# servo-ldr.net
KiCad netlist of a schematic drawn in EAGLE
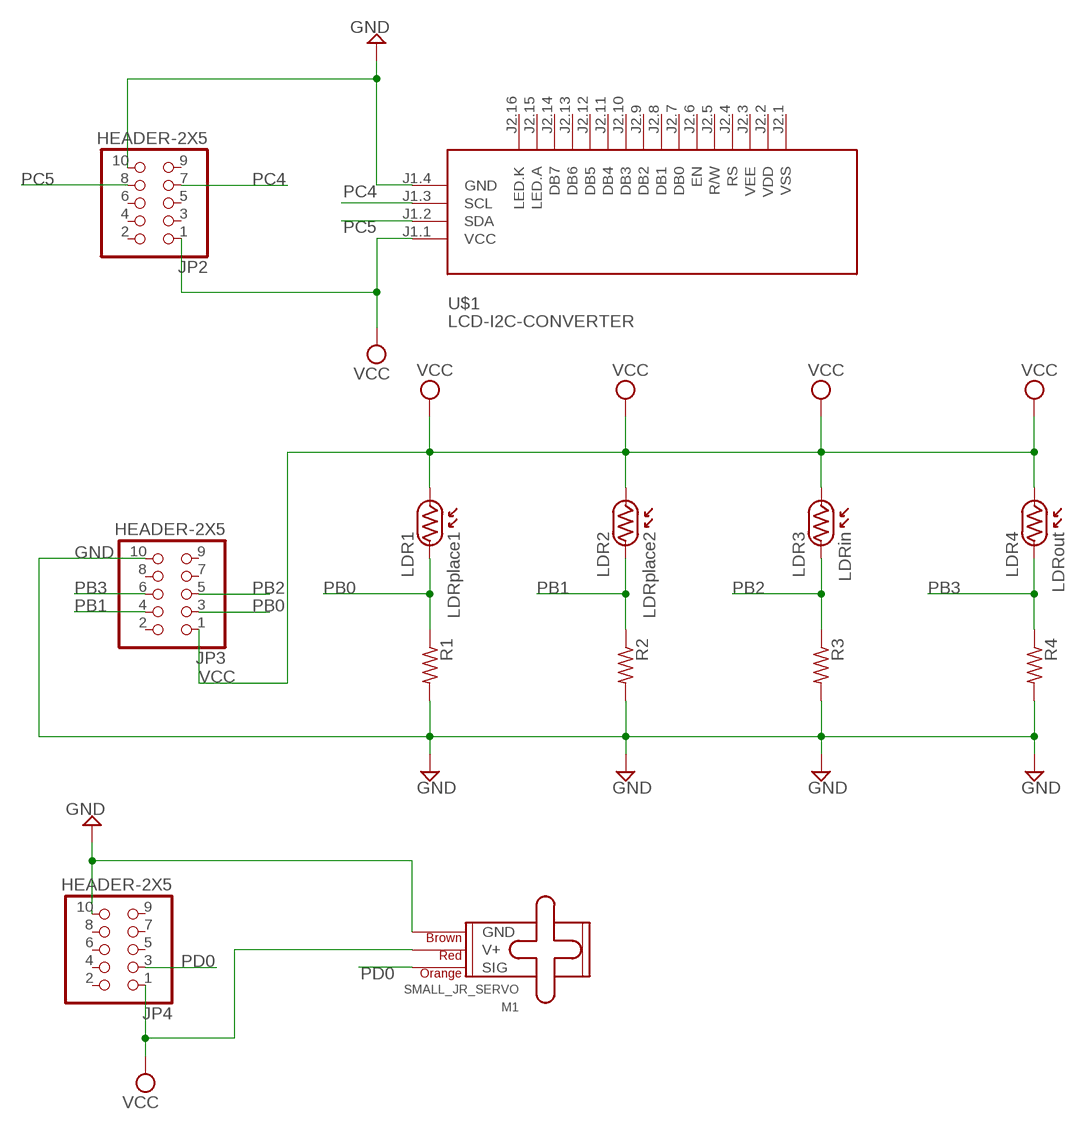
[diagram p0: schematic, sheet 1]

(export (version "E")
  (design (tool "Eeschema 10.0.6"))
  (components
    (comp (ref "JP2")
      (value "HEADER-2X5")
      (footprint "eagle-import:2X05")
      (libsource (lib "eagle-import") (part "HEADER-2X5"))
    )
    (comp (ref "JP3")
      (value "HEADER-2X5")
      (footprint "eagle-import:2X05")
      (libsource (lib "eagle-import") (part "HEADER-2X5"))
    )
    (comp (ref "JP4")
      (value "HEADER-2X5")
      (footprint "eagle-import:2X05")
      (libsource (lib "eagle-import") (part "HEADER-2X5"))
    )
    (comp (ref "LDR1")
      (value "LDRplace1")
      (footprint "eagle-import:3MM")
      (libsource (lib "eagle-import") (part "LDR"))
    )
    (comp (ref "LDR2")
      (value "LDRplace2")
      (footprint "eagle-import:3MM")
      (libsource (lib "eagle-import") (part "LDR"))
    )
    (comp (ref "LDR3")
      (value "LDRin")
      (footprint "eagle-import:3MM")
      (libsource (lib "eagle-import") (part "LDR"))
    )
    (comp (ref "LDR4")
      (value "LDRout")
      (footprint "eagle-import:3MM")
      (libsource (lib "eagle-import") (part "LDR"))
    )
    (comp (ref "M1")
      (value "SMALL_JR_SERVO")
      (footprint "eagle-import:1X03")
      (libsource (lib "eagle-import") (part "SMALL_JR_SERVO"))
    )
    (comp (ref "R1")
      (value "R-US_0207/10")
      (footprint "eagle-import:0207_10")
      (libsource (lib "eagle-import") (part "R-US_0207/10"))
    )
    (comp (ref "R2")
      (value "R-US_0207/10")
      (footprint "eagle-import:0207_10")
      (libsource (lib "eagle-import") (part "R-US_0207/10"))
    )
    (comp (ref "R3")
      (value "R-US_0207/10")
      (footprint "eagle-import:0207_10")
      (libsource (lib "eagle-import") (part "R-US_0207/10"))
    )
    (comp (ref "R4")
      (value "R-US_0207/10")
      (footprint "eagle-import:0207_10")
      (libsource (lib "eagle-import") (part "R-US_0207/10"))
    )
    (comp (ref "U$1")
      (value "LCD-I2C-CONVERTER")
      (footprint "eagle-import:LCD-I2C-CONVERTER")
      (libsource (lib "eagle-import") (part "LCD-I2C-CONVERTER"))
    )
  )
  (nets
    (net (code "1") (name "/PB0") (class "Default")
      (node (ref "JP3") (pin "3") (pinfunction "3_3") (pintype "passive"))
      (node (ref "LDR1") (pin "P$2") (pinfunction "P$2_P$2") (pintype "passive"))
      (node (ref "R1") (pin "1") (pinfunction "1_1") (pintype "passive"))
    )
    (net (code "2") (name "/PB1") (class "Default")
      (node (ref "JP3") (pin "4") (pinfunction "4_4") (pintype "passive"))
      (node (ref "LDR2") (pin "P$2") (pinfunction "P$2_P$2") (pintype "passive"))
      (node (ref "R2") (pin "1") (pinfunction "1_1") (pintype "passive"))
    )
    (net (code "3") (name "/PB2") (class "Default")
      (node (ref "JP3") (pin "5") (pinfunction "5_5") (pintype "passive"))
      (node (ref "LDR3") (pin "P$2") (pinfunction "P$2_P$2") (pintype "passive"))
      (node (ref "R3") (pin "1") (pinfunction "1_1") (pintype "passive"))
    )
    (net (code "4") (name "/PB3") (class "Default")
      (node (ref "JP3") (pin "6") (pinfunction "6_6") (pintype "passive"))
      (node (ref "LDR4") (pin "P$2") (pinfunction "P$2_P$2") (pintype "passive"))
      (node (ref "R4") (pin "1") (pinfunction "1_1") (pintype "passive"))
    )
    (net (code "5") (name "/PC4") (class "Default")
      (node (ref "JP2") (pin "7") (pinfunction "7_7") (pintype "passive"))
      (node (ref "U$1") (pin "J1.3") (pinfunction "SCL_J1.3") (pintype "bidirectional"))
    )
    (net (code "6") (name "/PC5") (class "Default")
      (node (ref "JP2") (pin "8") (pinfunction "8_8") (pintype "passive"))
      (node (ref "U$1") (pin "J1.2") (pinfunction "SDA_J1.2") (pintype "bidirectional"))
    )
    (net (code "7") (name "/PD0") (class "Default")
      (node (ref "JP4") (pin "3") (pinfunction "3_3") (pintype "passive"))
      (node (ref "M1") (pin "1") (pinfunction "SIG_1") (pintype "output"))
    )
    (net (code "8") (name "GND") (class "Default")
      (node (ref "JP2") (pin "10") (pinfunction "10_10") (pintype "passive"))
      (node (ref "JP3") (pin "10") (pinfunction "10_10") (pintype "passive"))
      (node (ref "JP4") (pin "10") (pinfunction "10_10") (pintype "passive"))
      (node (ref "M1") (pin "3") (pinfunction "GND_3") (pintype "passive"))
      (node (ref "R1") (pin "2") (pinfunction "2_2") (pintype "passive"))
      (node (ref "R2") (pin "2") (pinfunction "2_2") (pintype "passive"))
      (node (ref "R3") (pin "2") (pinfunction "2_2") (pintype "passive"))
      (node (ref "R4") (pin "2") (pinfunction "2_2") (pintype "passive"))
      (node (ref "U$1") (pin "J1.4") (pinfunction "GND_J1.4") (pintype "power_in"))
    )
    (net (code "9") (name "VCC") (class "Default")
      (node (ref "JP2") (pin "1") (pinfunction "1_1") (pintype "passive"))
      (node (ref "JP3") (pin "1") (pinfunction "1_1") (pintype "passive"))
      (node (ref "JP4") (pin "1") (pinfunction "1_1") (pintype "passive"))
      (node (ref "LDR1") (pin "P$1") (pinfunction "P$1_P$1") (pintype "passive"))
      (node (ref "LDR2") (pin "P$1") (pinfunction "P$1_P$1") (pintype "passive"))
      (node (ref "LDR3") (pin "P$1") (pinfunction "P$1_P$1") (pintype "passive"))
      (node (ref "LDR4") (pin "P$1") (pinfunction "P$1_P$1") (pintype "passive"))
      (node (ref "M1") (pin "2") (pinfunction "V+_2") (pintype "passive"))
      (node (ref "U$1") (pin "J1.1") (pinfunction "VCC_J1.1") (pintype "power_in"))
    )
    (net (code "10") (name "unconnected-(JP2-Pad2)") (class "Default")
      (node (ref "JP2") (pin "2") (pinfunction "2_2") (pintype "passive"))
    )
    (net (code "11") (name "unconnected-(JP2-Pad3)") (class "Default")
      (node (ref "JP2") (pin "3") (pinfunction "3_3") (pintype "passive"))
    )
    (net (code "12") (name "unconnected-(JP2-Pad4)") (class "Default")
      (node (ref "JP2") (pin "4") (pinfunction "4_4") (pintype "passive"))
    )
    (net (code "13") (name "unconnected-(JP2-Pad5)") (class "Default")
      (node (ref "JP2") (pin "5") (pinfunction "5_5") (pintype "passive"))
    )
    (net (code "14") (name "unconnected-(JP2-Pad6)") (class "Default")
      (node (ref "JP2") (pin "6") (pinfunction "6_6") (pintype "passive"))
    )
    (net (code "15") (name "unconnected-(JP2-Pad9)") (class "Default")
      (node (ref "JP2") (pin "9") (pinfunction "9_9") (pintype "passive"))
    )
    (net (code "16") (name "unconnected-(JP3-Pad2)") (class "Default")
      (node (ref "JP3") (pin "2") (pinfunction "2_2") (pintype "passive"))
    )
    (net (code "17") (name "unconnected-(JP3-Pad7)") (class "Default")
      (node (ref "JP3") (pin "7") (pinfunction "7_7") (pintype "passive"))
    )
    (net (code "18") (name "unconnected-(JP3-Pad8)") (class "Default")
      (node (ref "JP3") (pin "8") (pinfunction "8_8") (pintype "passive"))
    )
    (net (code "19") (name "unconnected-(JP3-Pad9)") (class "Default")
      (node (ref "JP3") (pin "9") (pinfunction "9_9") (pintype "passive"))
    )
    (net (code "20") (name "unconnected-(JP4-Pad2)") (class "Default")
      (node (ref "JP4") (pin "2") (pinfunction "2_2") (pintype "passive"))
    )
    (net (code "21") (name "unconnected-(JP4-Pad4)") (class "Default")
      (node (ref "JP4") (pin "4") (pinfunction "4_4") (pintype "passive"))
    )
    (net (code "22") (name "unconnected-(JP4-Pad5)") (class "Default")
      (node (ref "JP4") (pin "5") (pinfunction "5_5") (pintype "passive"))
    )
    (net (code "23") (name "unconnected-(JP4-Pad6)") (class "Default")
      (node (ref "JP4") (pin "6") (pinfunction "6_6") (pintype "passive"))
    )
    (net (code "24") (name "unconnected-(JP4-Pad7)") (class "Default")
      (node (ref "JP4") (pin "7") (pinfunction "7_7") (pintype "passive"))
    )
    (net (code "25") (name "unconnected-(JP4-Pad8)") (class "Default")
      (node (ref "JP4") (pin "8") (pinfunction "8_8") (pintype "passive"))
    )
    (net (code "26") (name "unconnected-(JP4-Pad9)") (class "Default")
      (node (ref "JP4") (pin "9") (pinfunction "9_9") (pintype "passive"))
    )
    (net (code "27") (name "unconnected-(U$1-DB0-PadJ2.7)") (class "Default")
      (node (ref "U$1") (pin "J2.7") (pinfunction "DB0_J2.7") (pintype "bidirectional"))
    )
    (net (code "28") (name "unconnected-(U$1-DB1-PadJ2.8)") (class "Default")
      (node (ref "U$1") (pin "J2.8") (pinfunction "DB1_J2.8") (pintype "bidirectional"))
    )
    (net (code "29") (name "unconnected-(U$1-DB2-PadJ2.9)") (class "Default")
      (node (ref "U$1") (pin "J2.9") (pinfunction "DB2_J2.9") (pintype "bidirectional"))
    )
    (net (code "30") (name "unconnected-(U$1-DB3-PadJ2.10)") (class "Default")
      (node (ref "U$1") (pin "J2.10") (pinfunction "DB3_J2.10") (pintype "bidirectional"))
    )
    (net (code "31") (name "unconnected-(U$1-DB4-PadJ2.11)") (class "Default")
      (node (ref "U$1") (pin "J2.11") (pinfunction "DB4_J2.11") (pintype "bidirectional"))
    )
    (net (code "32") (name "unconnected-(U$1-DB5-PadJ2.12)") (class "Default")
      (node (ref "U$1") (pin "J2.12") (pinfunction "DB5_J2.12") (pintype "bidirectional"))
    )
    (net (code "33") (name "unconnected-(U$1-DB6-PadJ2.13)") (class "Default")
      (node (ref "U$1") (pin "J2.13") (pinfunction "DB6_J2.13") (pintype "bidirectional"))
    )
    (net (code "34") (name "unconnected-(U$1-DB7-PadJ2.14)") (class "Default")
      (node (ref "U$1") (pin "J2.14") (pinfunction "DB7_J2.14") (pintype "bidirectional"))
    )
    (net (code "35") (name "unconnected-(U$1-EN-PadJ2.6)") (class "Default")
      (node (ref "U$1") (pin "J2.6") (pinfunction "EN_J2.6") (pintype "bidirectional"))
    )
    (net (code "36") (name "unconnected-(U$1-LED.A-PadJ2.15)") (class "Default")
      (node (ref "U$1") (pin "J2.15") (pinfunction "LED.A_J2.15") (pintype "bidirectional"))
    )
    (net (code "37") (name "unconnected-(U$1-LED.K-PadJ2.16)") (class "Default")
      (node (ref "U$1") (pin "J2.16") (pinfunction "LED.K_J2.16") (pintype "bidirectional"))
    )
    (net (code "38") (name "unconnected-(U$1-RS-PadJ2.4)") (class "Default")
      (node (ref "U$1") (pin "J2.4") (pinfunction "RS_J2.4") (pintype "bidirectional"))
    )
    (net (code "39") (name "unconnected-(U$1-R{slash}W-PadJ2.5)") (class "Default")
      (node (ref "U$1") (pin "J2.5") (pinfunction "R/W_J2.5") (pintype "bidirectional"))
    )
    (net (code "40") (name "unconnected-(U$1-VDD-PadJ2.2)") (class "Default")
      (node (ref "U$1") (pin "J2.2") (pinfunction "VDD_J2.2") (pintype "bidirectional"))
    )
    (net (code "41") (name "unconnected-(U$1-VEE-PadJ2.3)") (class "Default")
      (node (ref "U$1") (pin "J2.3") (pinfunction "VEE_J2.3") (pintype "bidirectional"))
    )
    (net (code "42") (name "unconnected-(U$1-VSS-PadJ2.1)") (class "Default")
      (node (ref "U$1") (pin "J2.1") (pinfunction "VSS_J2.1") (pintype "bidirectional"))
    )
  )
)
